# untitled.net
KiCad netlist of a schematic drawn in EAGLE
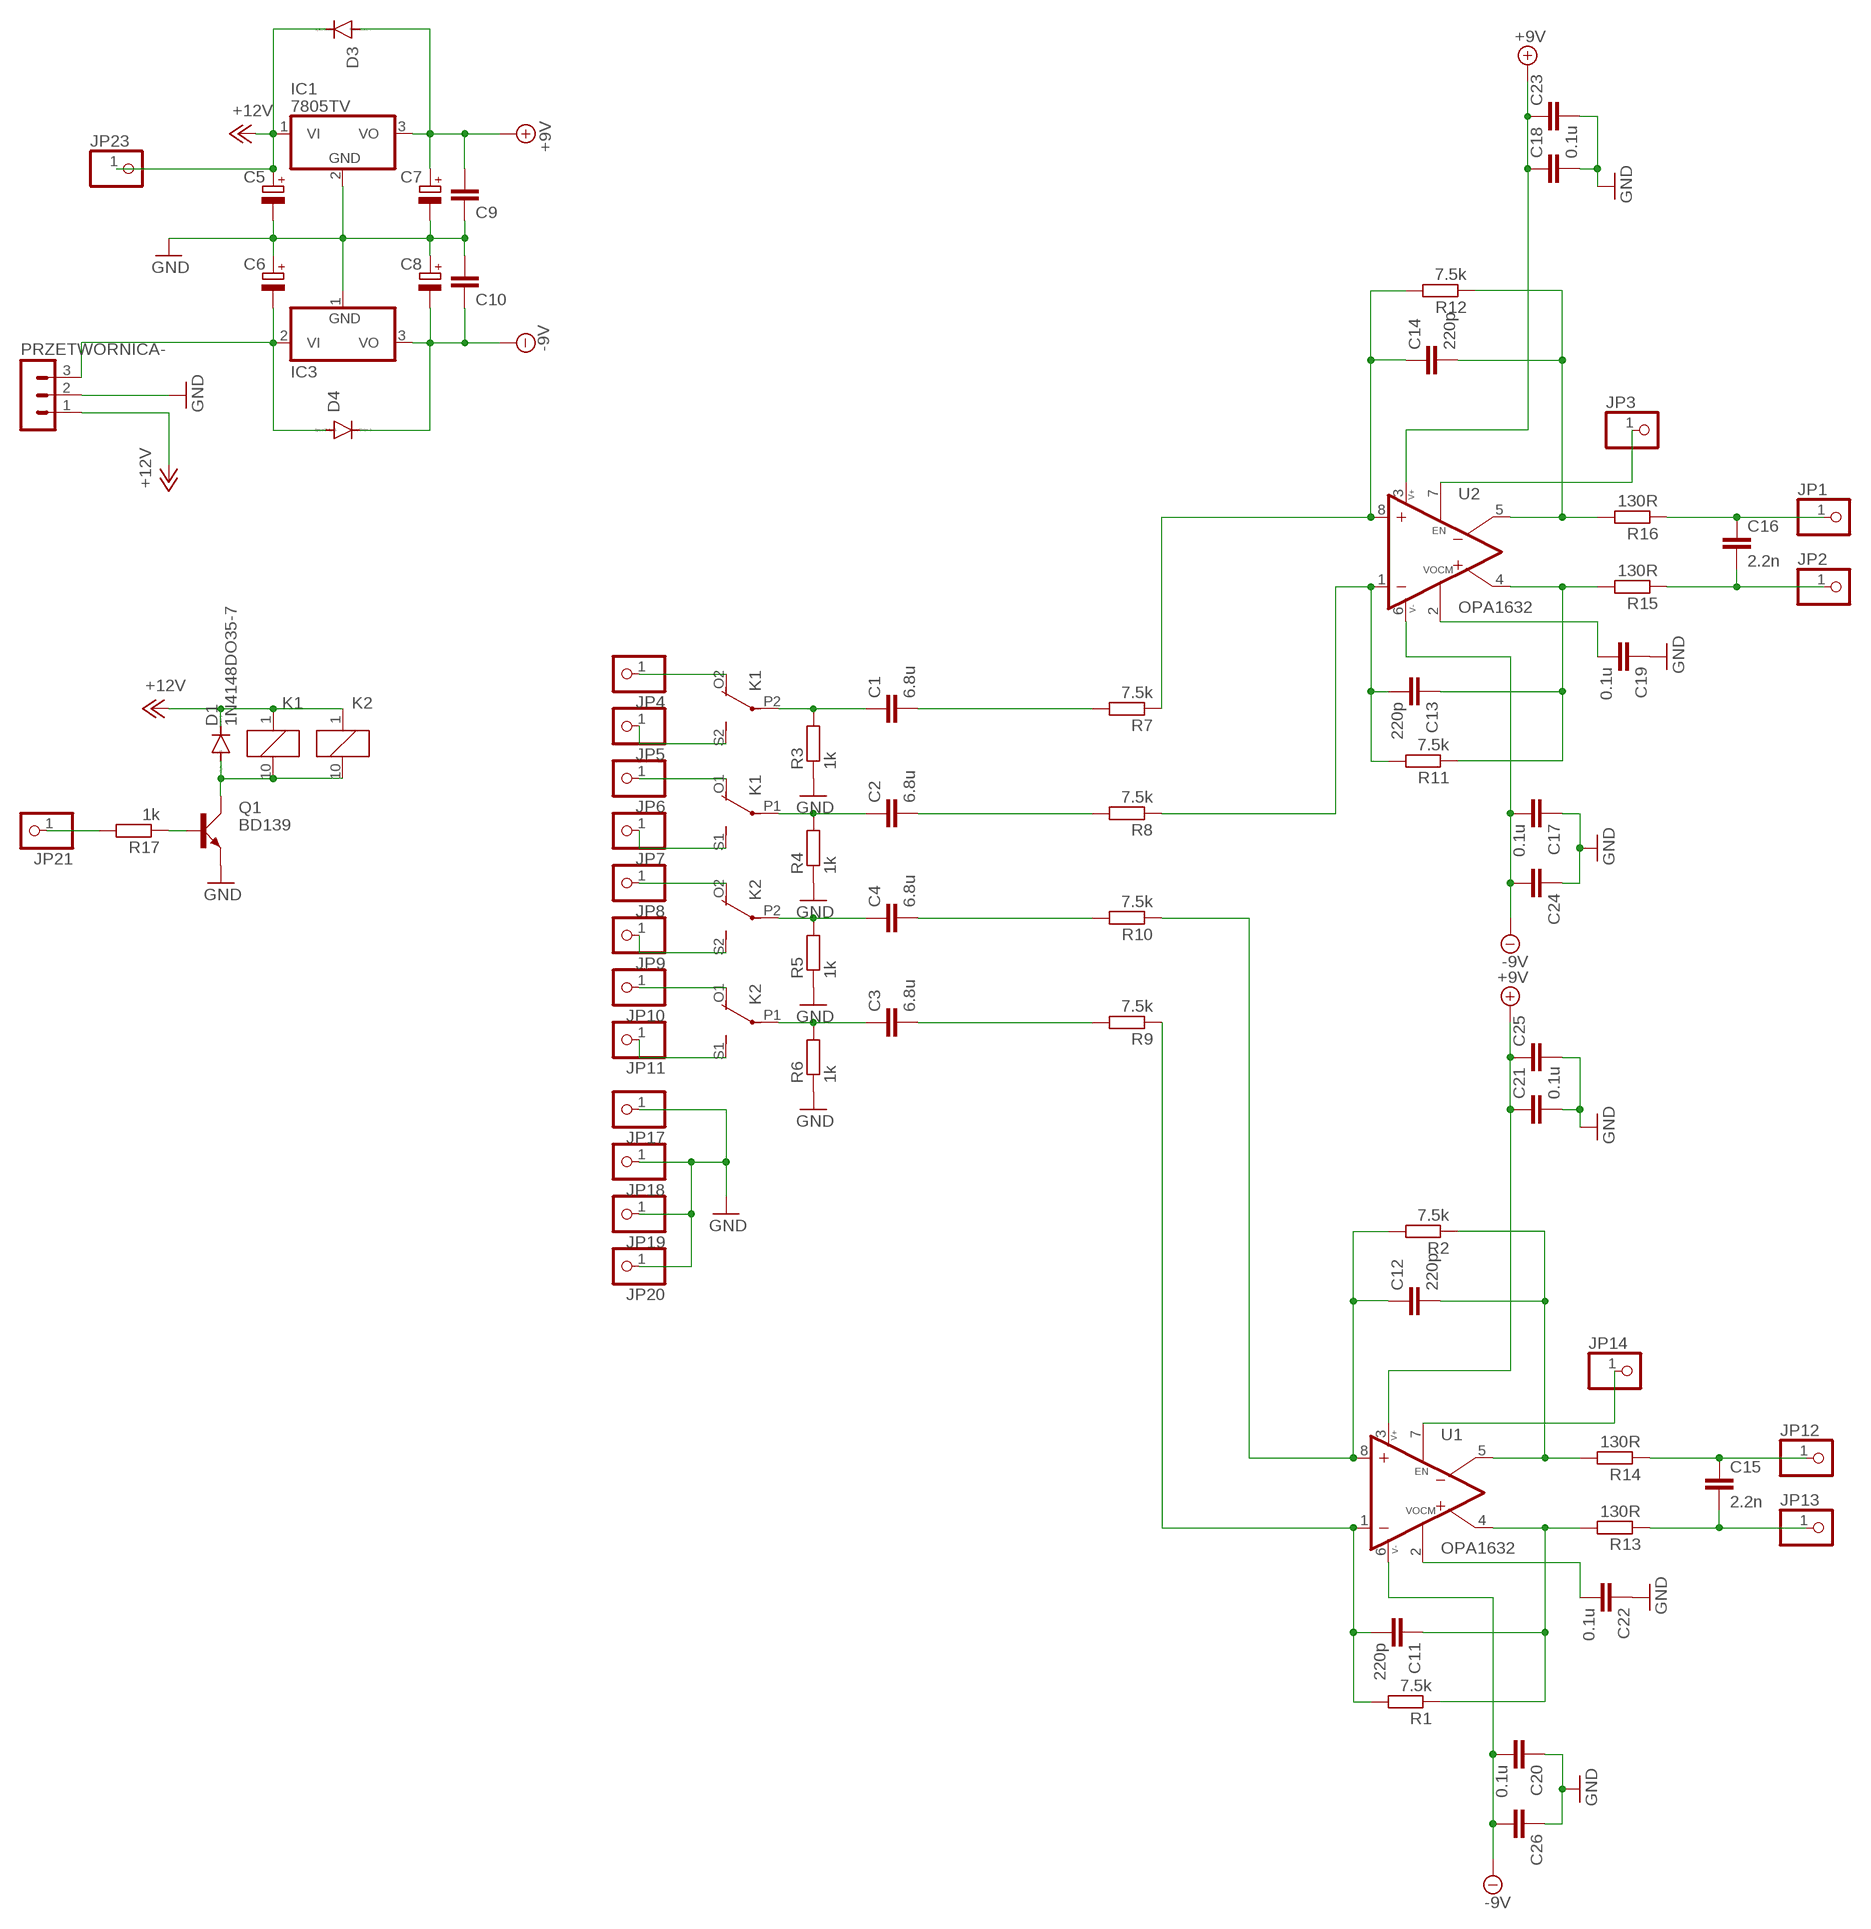
[diagram p0: schematic, sheet 1]

(export (version "E")
  (design (tool "Eeschema 10.0.6"))
  (components
    (comp (ref "C1")
      (value "6.8u")
      (footprint "eagle-import:C5B7.2")
      (libsource (lib "eagle-import") (part "C5/7.2"))
    )
    (comp (ref "C2")
      (value "6.8u")
      (footprint "eagle-import:C5B7.2")
      (libsource (lib "eagle-import") (part "C5/7.2"))
    )
    (comp (ref "C3")
      (value "6.8u")
      (footprint "eagle-import:C5B7.2")
      (libsource (lib "eagle-import") (part "C5/7.2"))
    )
    (comp (ref "C4")
      (value "6.8u")
      (footprint "eagle-import:C5B7.2")
      (libsource (lib "eagle-import") (part "C5/7.2"))
    )
    (comp (ref "C5")
      (value "CPOL-EUE3.5-8")
      (footprint "eagle-import:E3,5-8")
      (libsource (lib "eagle-import") (part "CPOL-EUE3.5-8"))
    )
    (comp (ref "C6")
      (value "CPOL-EUE3.5-8")
      (footprint "eagle-import:E3,5-8")
      (libsource (lib "eagle-import") (part "CPOL-EUE3.5-8"))
    )
    (comp (ref "C7")
      (value "CPOL-EUE3.5-8")
      (footprint "eagle-import:E3,5-8")
      (libsource (lib "eagle-import") (part "CPOL-EUE3.5-8"))
    )
    (comp (ref "C8")
      (value "CPOL-EUE3.5-8")
      (footprint "eagle-import:E3,5-8")
      (libsource (lib "eagle-import") (part "CPOL-EUE3.5-8"))
    )
    (comp (ref "C9")
      (value "C-EU050-024X044")
      (footprint "eagle-import:C050-024X044")
      (libsource (lib "eagle-import") (part "C-EU050-024X044"))
    )
    (comp (ref "C10")
      (value "C-EU050-024X044")
      (footprint "eagle-import:C050-024X044")
      (libsource (lib "eagle-import") (part "C-EU050-024X044"))
    )
    (comp (ref "C11")
      (value "220p")
      (footprint "eagle-import:C075-032X103")
      (libsource (lib "eagle-import") (part "C-EU075-032X103"))
    )
    (comp (ref "C12")
      (value "220p")
      (footprint "eagle-import:C075-032X103")
      (libsource (lib "eagle-import") (part "C-EU075-032X103"))
    )
    (comp (ref "C13")
      (value "220p")
      (footprint "eagle-import:C075-032X103")
      (libsource (lib "eagle-import") (part "C-EU075-032X103"))
    )
    (comp (ref "C14")
      (value "220p")
      (footprint "eagle-import:C075-032X103")
      (libsource (lib "eagle-import") (part "C-EU075-032X103"))
    )
    (comp (ref "C15")
      (value "2.2n")
      (footprint "eagle-import:C025-024X044")
      (libsource (lib "eagle-import") (part "C-EU025-024X044"))
    )
    (comp (ref "C16")
      (value "2.2n")
      (footprint "eagle-import:C025-024X044")
      (libsource (lib "eagle-import") (part "C-EU025-024X044"))
    )
    (comp (ref "C17")
      (value "0.1u")
      (footprint "eagle-import:C025-024X044")
      (libsource (lib "eagle-import") (part "C-EU025-024X044"))
    )
    (comp (ref "C18")
      (value "0.1u")
      (footprint "eagle-import:C025-024X044")
      (libsource (lib "eagle-import") (part "C-EU025-024X044"))
    )
    (comp (ref "C19")
      (value "0.1u")
      (footprint "eagle-import:C025-024X044")
      (libsource (lib "eagle-import") (part "C-EU025-024X044"))
    )
    (comp (ref "C20")
      (value "0.1u")
      (footprint "eagle-import:C025-024X044")
      (libsource (lib "eagle-import") (part "C-EU025-024X044"))
    )
    (comp (ref "C21")
      (value "0.1u")
      (footprint "eagle-import:C025-024X044")
      (libsource (lib "eagle-import") (part "C-EU025-024X044"))
    )
    (comp (ref "C22")
      (value "0.1u")
      (footprint "eagle-import:C025-024X044")
      (libsource (lib "eagle-import") (part "C-EU025-024X044"))
    )
    (comp (ref "C23")
      (value "C-EU050-024X044")
      (footprint "eagle-import:C050-024X044")
      (libsource (lib "eagle-import") (part "C-EU050-024X044"))
    )
    (comp (ref "C24")
      (value "C-EU050-024X044")
      (footprint "eagle-import:C050-024X044")
      (libsource (lib "eagle-import") (part "C-EU050-024X044"))
    )
    (comp (ref "C25")
      (value "C-EU050-024X044")
      (footprint "eagle-import:C050-024X044")
      (libsource (lib "eagle-import") (part "C-EU050-024X044"))
    )
    (comp (ref "C26")
      (value "C-EU050-024X044")
      (footprint "eagle-import:C050-024X044")
      (libsource (lib "eagle-import") (part "C-EU050-024X044"))
    )
    (comp (ref "D1")
      (value "1N4148DO35-7")
      (footprint "eagle-import:DO35-7")
      (libsource (lib "eagle-import") (part "1N4148DO35-7"))
    )
    (comp (ref "D3")
      (value "1N4148DO35-7")
      (footprint "eagle-import:DO35-7")
      (libsource (lib "eagle-import") (part "1N4148DO35-7"))
    )
    (comp (ref "D4")
      (value "1N4148DO35-7")
      (footprint "eagle-import:DO35-7")
      (libsource (lib "eagle-import") (part "1N4148DO35-7"))
    )
    (comp (ref "IC1")
      (value "7805TV")
      (footprint "eagle-import:TO220V")
      (libsource (lib "eagle-import") (part "78TV05"))
    )
    (comp (ref "IC3")
      (value "79")
      (footprint "eagle-import:TO220V")
      (libsource (lib "eagle-import") (part "79"))
    )
    (comp (ref "JP1")
      (value "PINHD-1X1")
      (footprint "eagle-import:1X01")
      (libsource (lib "eagle-import") (part "PINHD-1X1"))
    )
    (comp (ref "JP2")
      (value "PINHD-1X1")
      (footprint "eagle-import:1X01")
      (libsource (lib "eagle-import") (part "PINHD-1X1"))
    )
    (comp (ref "JP3")
      (value "PINHD-1X1")
      (footprint "eagle-import:1X01")
      (libsource (lib "eagle-import") (part "PINHD-1X1"))
    )
    (comp (ref "JP4")
      (value "PINHD-1X1")
      (footprint "eagle-import:1X01")
      (libsource (lib "eagle-import") (part "PINHD-1X1"))
    )
    (comp (ref "JP5")
      (value "PINHD-1X1")
      (footprint "eagle-import:1X01")
      (libsource (lib "eagle-import") (part "PINHD-1X1"))
    )
    (comp (ref "JP6")
      (value "PINHD-1X1")
      (footprint "eagle-import:1X01")
      (libsource (lib "eagle-import") (part "PINHD-1X1"))
    )
    (comp (ref "JP7")
      (value "PINHD-1X1")
      (footprint "eagle-import:1X01")
      (libsource (lib "eagle-import") (part "PINHD-1X1"))
    )
    (comp (ref "JP8")
      (value "PINHD-1X1")
      (footprint "eagle-import:1X01")
      (libsource (lib "eagle-import") (part "PINHD-1X1"))
    )
    (comp (ref "JP9")
      (value "PINHD-1X1")
      (footprint "eagle-import:1X01")
      (libsource (lib "eagle-import") (part "PINHD-1X1"))
    )
    (comp (ref "JP10")
      (value "PINHD-1X1")
      (footprint "eagle-import:1X01")
      (libsource (lib "eagle-import") (part "PINHD-1X1"))
    )
    (comp (ref "JP11")
      (value "PINHD-1X1")
      (footprint "eagle-import:1X01")
      (libsource (lib "eagle-import") (part "PINHD-1X1"))
    )
    (comp (ref "JP12")
      (value "PINHD-1X1")
      (footprint "eagle-import:1X01")
      (libsource (lib "eagle-import") (part "PINHD-1X1"))
    )
    (comp (ref "JP13")
      (value "PINHD-1X1")
      (footprint "eagle-import:1X01")
      (libsource (lib "eagle-import") (part "PINHD-1X1"))
    )
    (comp (ref "JP14")
      (value "PINHD-1X1")
      (footprint "eagle-import:1X01")
      (libsource (lib "eagle-import") (part "PINHD-1X1"))
    )
    (comp (ref "JP17")
      (value "PINHD-1X1")
      (footprint "eagle-import:1X01")
      (libsource (lib "eagle-import") (part "PINHD-1X1"))
    )
    (comp (ref "JP18")
      (value "PINHD-1X1")
      (footprint "eagle-import:1X01")
      (libsource (lib "eagle-import") (part "PINHD-1X1"))
    )
    (comp (ref "JP19")
      (value "PINHD-1X1")
      (footprint "eagle-import:1X01")
      (libsource (lib "eagle-import") (part "PINHD-1X1"))
    )
    (comp (ref "JP20")
      (value "PINHD-1X1")
      (footprint "eagle-import:1X01")
      (libsource (lib "eagle-import") (part "PINHD-1X1"))
    )
    (comp (ref "JP21")
      (value "PINHD-1X1")
      (footprint "eagle-import:1X01")
      (libsource (lib "eagle-import") (part "PINHD-1X1"))
    )
    (comp (ref "JP23")
      (value "PINHD-1X1")
      (footprint "eagle-import:1X01")
      (libsource (lib "eagle-import") (part "PINHD-1X1"))
    )
    (comp (ref "K1")
      (value "G6H2-100")
      (footprint "eagle-import:G6H2-100")
      (libsource (lib "eagle-import") (part "G6H2-100"))
    )
    (comp (ref "K2")
      (value "G6H2-100")
      (footprint "eagle-import:G6H2-100")
      (libsource (lib "eagle-import") (part "G6H2-100"))
    )
    (comp (ref "PRZETWORNICA-")
      (value "MA03-1")
      (footprint "eagle-import:MA03-1")
      (libsource (lib "eagle-import") (part "MA03-1"))
    )
    (comp (ref "Q1")
      (value "BD139")
      (footprint "eagle-import:TO126AV")
      (libsource (lib "eagle-import") (part "BD139"))
    )
    (comp (ref "R1")
      (value "7.5k")
      (footprint "eagle-import:0204_7")
      (libsource (lib "eagle-import") (part "R-EU_0204/7"))
    )
    (comp (ref "R2")
      (value "7.5k")
      (footprint "eagle-import:0204_7")
      (libsource (lib "eagle-import") (part "R-EU_0204/7"))
    )
    (comp (ref "R3")
      (value "1k")
      (footprint "eagle-import:0204_7")
      (libsource (lib "eagle-import") (part "R-EU_0204/7"))
    )
    (comp (ref "R4")
      (value "1k")
      (footprint "eagle-import:0204_7")
      (libsource (lib "eagle-import") (part "R-EU_0204/7"))
    )
    (comp (ref "R5")
      (value "1k")
      (footprint "eagle-import:0204_7")
      (libsource (lib "eagle-import") (part "R-EU_0204/7"))
    )
    (comp (ref "R6")
      (value "1k")
      (footprint "eagle-import:0204_7")
      (libsource (lib "eagle-import") (part "R-EU_0204/7"))
    )
    (comp (ref "R7")
      (value "7.5k")
      (footprint "eagle-import:0204_5")
      (libsource (lib "eagle-import") (part "R-EU_0204/5"))
    )
    (comp (ref "R8")
      (value "7.5k")
      (footprint "eagle-import:0204_5")
      (libsource (lib "eagle-import") (part "R-EU_0204/5"))
    )
    (comp (ref "R9")
      (value "7.5k")
      (footprint "eagle-import:0204_5")
      (libsource (lib "eagle-import") (part "R-EU_0204/5"))
    )
    (comp (ref "R10")
      (value "7.5k")
      (footprint "eagle-import:0204_5")
      (libsource (lib "eagle-import") (part "R-EU_0204/5"))
    )
    (comp (ref "R11")
      (value "7.5k")
      (footprint "eagle-import:0204_7")
      (libsource (lib "eagle-import") (part "R-EU_0204/7"))
    )
    (comp (ref "R12")
      (value "7.5k")
      (footprint "eagle-import:0204_7")
      (libsource (lib "eagle-import") (part "R-EU_0204/7"))
    )
    (comp (ref "R13")
      (value "130R")
      (footprint "eagle-import:0204_5")
      (libsource (lib "eagle-import") (part "R-EU_0204/5"))
    )
    (comp (ref "R14")
      (value "130R")
      (footprint "eagle-import:0204_5")
      (libsource (lib "eagle-import") (part "R-EU_0204/5"))
    )
    (comp (ref "R15")
      (value "130R")
      (footprint "eagle-import:0204_5")
      (libsource (lib "eagle-import") (part "R-EU_0204/5"))
    )
    (comp (ref "R16")
      (value "130R")
      (footprint "eagle-import:0204_5")
      (libsource (lib "eagle-import") (part "R-EU_0204/5"))
    )
    (comp (ref "R17")
      (value "1k")
      (footprint "eagle-import:0204_7")
      (libsource (lib "eagle-import") (part "R-EU_0204/7"))
    )
    (comp (ref "U1")
      (value "OPA1632")
      (footprint "eagle-import:PRZEJSCIOWKA")
      (libsource (lib "eagle-import") (part "OPA1632"))
    )
    (comp (ref "U2")
      (value "OPA1632")
      (footprint "eagle-import:PRZEJSCIOWKA")
      (libsource (lib "eagle-import") (part "OPA1632"))
    )
  )
  (nets
    (net (code "1") (name "+9V") (class "Default")
      (node (ref "C18") (pin "1") (pinfunction "1_1") (pintype "passive"))
      (node (ref "C21") (pin "1") (pinfunction "1_1") (pintype "passive"))
      (node (ref "C23") (pin "1") (pinfunction "1_1") (pintype "passive"))
      (node (ref "C25") (pin "1") (pinfunction "1_1") (pintype "passive"))
      (node (ref "C7") (pin "+") (pinfunction "+_+") (pintype "passive"))
      (node (ref "C9") (pin "2") (pinfunction "2_2") (pintype "passive"))
      (node (ref "D3") (pin "A") (pinfunction "A_A") (pintype "passive"))
      (node (ref "IC1") (pin "3") (pinfunction "VO_3") (pintype "passive"))
      (node (ref "U1") (pin "3") (pinfunction "V+_3") (pintype "power_in"))
      (node (ref "U2") (pin "3") (pinfunction "V+_3") (pintype "power_in"))
    )
    (net (code "2") (name "+12V") (class "Default")
      (node (ref "C5") (pin "+") (pinfunction "+_+") (pintype "passive"))
      (node (ref "D1") (pin "C") (pinfunction "C_C") (pintype "passive"))
      (node (ref "D3") (pin "C") (pinfunction "C_C") (pintype "passive"))
      (node (ref "IC1") (pin "1") (pinfunction "VI_1") (pintype "input"))
      (node (ref "JP23") (pin "1") (pinfunction "1_1") (pintype "passive"))
      (node (ref "K1") (pin "1") (pinfunction "1_1") (pintype "passive"))
      (node (ref "K2") (pin "1") (pinfunction "1_1") (pintype "passive"))
      (node (ref "PRZETWORNICA-") (pin "1") (pinfunction "1_1") (pintype "passive"))
    )
    (net (code "3") (name "-9V") (class "Default")
      (node (ref "C10") (pin "1") (pinfunction "1_1") (pintype "passive"))
      (node (ref "C17") (pin "2") (pinfunction "2_2") (pintype "passive"))
      (node (ref "C20") (pin "2") (pinfunction "2_2") (pintype "passive"))
      (node (ref "C24") (pin "2") (pinfunction "2_2") (pintype "passive"))
      (node (ref "C26") (pin "2") (pinfunction "2_2") (pintype "passive"))
      (node (ref "C8") (pin "-") (pinfunction "-_-") (pintype "passive"))
      (node (ref "D4") (pin "C") (pinfunction "C_C") (pintype "passive"))
      (node (ref "IC3") (pin "3") (pinfunction "VO_3") (pintype "passive"))
      (node (ref "U1") (pin "6") (pinfunction "V-_6") (pintype "power_in"))
      (node (ref "U2") (pin "6") (pinfunction "V-_6") (pintype "power_in"))
    )
    (net (code "4") (name "GND") (class "Default")
      (node (ref "C10") (pin "2") (pinfunction "2_2") (pintype "passive"))
      (node (ref "C17") (pin "1") (pinfunction "1_1") (pintype "passive"))
      (node (ref "C18") (pin "2") (pinfunction "2_2") (pintype "passive"))
      (node (ref "C19") (pin "1") (pinfunction "1_1") (pintype "passive"))
      (node (ref "C20") (pin "1") (pinfunction "1_1") (pintype "passive"))
      (node (ref "C21") (pin "2") (pinfunction "2_2") (pintype "passive"))
      (node (ref "C22") (pin "1") (pinfunction "1_1") (pintype "passive"))
      (node (ref "C23") (pin "2") (pinfunction "2_2") (pintype "passive"))
      (node (ref "C24") (pin "1") (pinfunction "1_1") (pintype "passive"))
      (node (ref "C25") (pin "2") (pinfunction "2_2") (pintype "passive"))
      (node (ref "C26") (pin "1") (pinfunction "1_1") (pintype "passive"))
      (node (ref "C5") (pin "-") (pinfunction "-_-") (pintype "passive"))
      (node (ref "C6") (pin "+") (pinfunction "+_+") (pintype "passive"))
      (node (ref "C7") (pin "-") (pinfunction "-_-") (pintype "passive"))
      (node (ref "C8") (pin "+") (pinfunction "+_+") (pintype "passive"))
      (node (ref "C9") (pin "1") (pinfunction "1_1") (pintype "passive"))
      (node (ref "IC1") (pin "2") (pinfunction "GND_2") (pintype "passive"))
      (node (ref "IC3") (pin "1") (pinfunction "GND_1") (pintype "passive"))
      (node (ref "JP17") (pin "1") (pinfunction "1_1") (pintype "passive"))
      (node (ref "JP18") (pin "1") (pinfunction "1_1") (pintype "passive"))
      (node (ref "JP19") (pin "1") (pinfunction "1_1") (pintype "passive"))
      (node (ref "JP20") (pin "1") (pinfunction "1_1") (pintype "passive"))
      (node (ref "PRZETWORNICA-") (pin "2") (pinfunction "2_2") (pintype "passive"))
      (node (ref "Q1") (pin "E") (pinfunction "E_E") (pintype "passive"))
      (node (ref "R3") (pin "1") (pinfunction "1_1") (pintype "passive"))
      (node (ref "R4") (pin "1") (pinfunction "1_1") (pintype "passive"))
      (node (ref "R5") (pin "1") (pinfunction "1_1") (pintype "passive"))
      (node (ref "R6") (pin "1") (pinfunction "1_1") (pintype "passive"))
    )
    (net (code "5") (name "Net-(C1-Pad2)") (class "Default")
      (node (ref "C1") (pin "2") (pinfunction "2_2") (pintype "passive"))
      (node (ref "R7") (pin "2") (pinfunction "2_2") (pintype "passive"))
    )
    (net (code "6") (name "Net-(C2-Pad2)") (class "Default")
      (node (ref "C2") (pin "2") (pinfunction "2_2") (pintype "passive"))
      (node (ref "R8") (pin "2") (pinfunction "2_2") (pintype "passive"))
    )
    (net (code "7") (name "Net-(C3-Pad2)") (class "Default")
      (node (ref "C3") (pin "2") (pinfunction "2_2") (pintype "passive"))
      (node (ref "R9") (pin "2") (pinfunction "2_2") (pintype "passive"))
    )
    (net (code "8") (name "Net-(C4-Pad2)") (class "Default")
      (node (ref "C4") (pin "2") (pinfunction "2_2") (pintype "passive"))
      (node (ref "R10") (pin "2") (pinfunction "2_2") (pintype "passive"))
    )
    (net (code "9") (name "Net-(C15-Pad1)") (class "Default")
      (node (ref "C15") (pin "1") (pinfunction "1_1") (pintype "passive"))
      (node (ref "JP12") (pin "1") (pinfunction "1_1") (pintype "passive"))
      (node (ref "R14") (pin "1") (pinfunction "1_1") (pintype "passive"))
    )
    (net (code "10") (name "Net-(C15-Pad2)") (class "Default")
      (node (ref "C15") (pin "2") (pinfunction "2_2") (pintype "passive"))
      (node (ref "JP13") (pin "1") (pinfunction "1_1") (pintype "passive"))
      (node (ref "R13") (pin "1") (pinfunction "1_1") (pintype "passive"))
    )
    (net (code "11") (name "Net-(C16-Pad1)") (class "Default")
      (node (ref "C16") (pin "1") (pinfunction "1_1") (pintype "passive"))
      (node (ref "JP1") (pin "1") (pinfunction "1_1") (pintype "passive"))
      (node (ref "R16") (pin "1") (pinfunction "1_1") (pintype "passive"))
    )
    (net (code "12") (name "Net-(C16-Pad2)") (class "Default")
      (node (ref "C16") (pin "2") (pinfunction "2_2") (pintype "passive"))
      (node (ref "JP2") (pin "1") (pinfunction "1_1") (pintype "passive"))
      (node (ref "R15") (pin "1") (pinfunction "1_1") (pintype "passive"))
    )
    (net (code "13") (name "Net-(IC3-VI)") (class "Default")
      (node (ref "C6") (pin "-") (pinfunction "-_-") (pintype "passive"))
      (node (ref "D4") (pin "A") (pinfunction "A_A") (pintype "passive"))
      (node (ref "IC3") (pin "2") (pinfunction "VI_2") (pintype "input"))
      (node (ref "PRZETWORNICA-") (pin "3") (pinfunction "3_3") (pintype "passive"))
    )
    (net (code "14") (name "Net-(JP21-Pad1)") (class "Default")
      (node (ref "JP21") (pin "1") (pinfunction "1_1") (pintype "passive"))
      (node (ref "R17") (pin "2") (pinfunction "2_2") (pintype "passive"))
    )
    (net (code "15") (name "Net-(K1A-2)") (class "Default")
      (node (ref "D1") (pin "A") (pinfunction "A_A") (pintype "passive"))
      (node (ref "K1") (pin "10") (pinfunction "2_10") (pintype "passive"))
      (node (ref "K2") (pin "10") (pinfunction "2_10") (pintype "passive"))
      (node (ref "Q1") (pin "C") (pinfunction "C_C") (pintype "passive"))
    )
    (net (code "16") (name "Net-(K1B-O)") (class "Default")
      (node (ref "JP6") (pin "1") (pinfunction "1_1") (pintype "passive"))
      (node (ref "K1") (pin "O1") (pinfunction "O_O1") (pintype "passive"))
    )
    (net (code "17") (name "Net-(K1B-P)") (class "Default")
      (node (ref "C2") (pin "1") (pinfunction "1_1") (pintype "passive"))
      (node (ref "K1") (pin "P1") (pinfunction "P_P1") (pintype "passive"))
      (node (ref "R4") (pin "2") (pinfunction "2_2") (pintype "passive"))
    )
    (net (code "18") (name "Net-(K1B-S)") (class "Default")
      (node (ref "JP7") (pin "1") (pinfunction "1_1") (pintype "passive"))
      (node (ref "K1") (pin "S1") (pinfunction "S_S1") (pintype "passive"))
    )
    (net (code "19") (name "Net-(K1C-O)") (class "Default")
      (node (ref "JP4") (pin "1") (pinfunction "1_1") (pintype "passive"))
      (node (ref "K1") (pin "O2") (pinfunction "O_O2") (pintype "passive"))
    )
    (net (code "20") (name "Net-(K1C-P)") (class "Default")
      (node (ref "C1") (pin "1") (pinfunction "1_1") (pintype "passive"))
      (node (ref "K1") (pin "P2") (pinfunction "P_P2") (pintype "passive"))
      (node (ref "R3") (pin "2") (pinfunction "2_2") (pintype "passive"))
    )
    (net (code "21") (name "Net-(K1C-S)") (class "Default")
      (node (ref "JP5") (pin "1") (pinfunction "1_1") (pintype "passive"))
      (node (ref "K1") (pin "S2") (pinfunction "S_S2") (pintype "passive"))
    )
    (net (code "22") (name "Net-(K2B-O)") (class "Default")
      (node (ref "JP10") (pin "1") (pinfunction "1_1") (pintype "passive"))
      (node (ref "K2") (pin "O1") (pinfunction "O_O1") (pintype "passive"))
    )
    (net (code "23") (name "Net-(K2B-P)") (class "Default")
      (node (ref "C3") (pin "1") (pinfunction "1_1") (pintype "passive"))
      (node (ref "K2") (pin "P1") (pinfunction "P_P1") (pintype "passive"))
      (node (ref "R6") (pin "2") (pinfunction "2_2") (pintype "passive"))
    )
    (net (code "24") (name "Net-(K2B-S)") (class "Default")
      (node (ref "JP11") (pin "1") (pinfunction "1_1") (pintype "passive"))
      (node (ref "K2") (pin "S1") (pinfunction "S_S1") (pintype "passive"))
    )
    (net (code "25") (name "Net-(K2C-O)") (class "Default")
      (node (ref "JP8") (pin "1") (pinfunction "1_1") (pintype "passive"))
      (node (ref "K2") (pin "O2") (pinfunction "O_O2") (pintype "passive"))
    )
    (net (code "26") (name "Net-(K2C-P)") (class "Default")
      (node (ref "C4") (pin "1") (pinfunction "1_1") (pintype "passive"))
      (node (ref "K2") (pin "P2") (pinfunction "P_P2") (pintype "passive"))
      (node (ref "R5") (pin "2") (pinfunction "2_2") (pintype "passive"))
    )
    (net (code "27") (name "Net-(K2C-S)") (class "Default")
      (node (ref "JP9") (pin "1") (pinfunction "1_1") (pintype "passive"))
      (node (ref "K2") (pin "S2") (pinfunction "S_S2") (pintype "passive"))
    )
    (net (code "28") (name "Net-(Q1-PadB)") (class "Default")
      (node (ref "Q1") (pin "B") (pinfunction "B_B") (pintype "passive"))
      (node (ref "R17") (pin "1") (pinfunction "1_1") (pintype "passive"))
    )
    (net (code "29") (name "Net-(U1-+IN)") (class "Default")
      (node (ref "C12") (pin "1") (pinfunction "1_1") (pintype "passive"))
      (node (ref "R10") (pin "1") (pinfunction "1_1") (pintype "passive"))
      (node (ref "R2") (pin "2") (pinfunction "2_2") (pintype "passive"))
      (node (ref "U1") (pin "8") (pinfunction "+IN_8") (pintype "input"))
    )
    (net (code "30") (name "Net-(U1-+OUT)") (class "Default")
      (node (ref "C11") (pin "1") (pinfunction "1_1") (pintype "passive"))
      (node (ref "R1") (pin "1") (pinfunction "1_1") (pintype "passive"))
      (node (ref "R13") (pin "2") (pinfunction "2_2") (pintype "passive"))
      (node (ref "U1") (pin "4") (pinfunction "+OUT_4") (pintype "output"))
    )
    (net (code "31") (name "Net-(U1--IN)") (class "Default")
      (node (ref "C11") (pin "2") (pinfunction "2_2") (pintype "passive"))
      (node (ref "R1") (pin "2") (pinfunction "2_2") (pintype "passive"))
      (node (ref "R9") (pin "1") (pinfunction "1_1") (pintype "passive"))
      (node (ref "U1") (pin "1") (pinfunction "-IN_1") (pintype "input"))
    )
    (net (code "32") (name "Net-(U1--OUT)") (class "Default")
      (node (ref "C12") (pin "2") (pinfunction "2_2") (pintype "passive"))
      (node (ref "R14") (pin "2") (pinfunction "2_2") (pintype "passive"))
      (node (ref "R2") (pin "1") (pinfunction "1_1") (pintype "passive"))
      (node (ref "U1") (pin "5") (pinfunction "-OUT_5") (pintype "output"))
    )
    (net (code "33") (name "Net-(U1-EN)") (class "Default")
      (node (ref "JP14") (pin "1") (pinfunction "1_1") (pintype "passive"))
      (node (ref "U1") (pin "7") (pinfunction "EN_7") (pintype "input"))
    )
    (net (code "34") (name "Net-(U1-VOCM)") (class "Default")
      (node (ref "C22") (pin "2") (pinfunction "2_2") (pintype "passive"))
      (node (ref "U1") (pin "2") (pinfunction "VOCM_2") (pintype "input"))
    )
    (net (code "35") (name "Net-(U2-+IN)") (class "Default")
      (node (ref "C14") (pin "1") (pinfunction "1_1") (pintype "passive"))
      (node (ref "R12") (pin "2") (pinfunction "2_2") (pintype "passive"))
      (node (ref "R7") (pin "1") (pinfunction "1_1") (pintype "passive"))
      (node (ref "U2") (pin "8") (pinfunction "+IN_8") (pintype "input"))
    )
    (net (code "36") (name "Net-(U2-+OUT)") (class "Default")
      (node (ref "C13") (pin "1") (pinfunction "1_1") (pintype "passive"))
      (node (ref "R11") (pin "1") (pinfunction "1_1") (pintype "passive"))
      (node (ref "R15") (pin "2") (pinfunction "2_2") (pintype "passive"))
      (node (ref "U2") (pin "4") (pinfunction "+OUT_4") (pintype "output"))
    )
    (net (code "37") (name "Net-(U2--IN)") (class "Default")
      (node (ref "C13") (pin "2") (pinfunction "2_2") (pintype "passive"))
      (node (ref "R11") (pin "2") (pinfunction "2_2") (pintype "passive"))
      (node (ref "R8") (pin "1") (pinfunction "1_1") (pintype "passive"))
      (node (ref "U2") (pin "1") (pinfunction "-IN_1") (pintype "input"))
    )
    (net (code "38") (name "Net-(U2--OUT)") (class "Default")
      (node (ref "C14") (pin "2") (pinfunction "2_2") (pintype "passive"))
      (node (ref "R12") (pin "1") (pinfunction "1_1") (pintype "passive"))
      (node (ref "R16") (pin "2") (pinfunction "2_2") (pintype "passive"))
      (node (ref "U2") (pin "5") (pinfunction "-OUT_5") (pintype "output"))
    )
    (net (code "39") (name "Net-(U2-EN)") (class "Default")
      (node (ref "JP3") (pin "1") (pinfunction "1_1") (pintype "passive"))
      (node (ref "U2") (pin "7") (pinfunction "EN_7") (pintype "input"))
    )
    (net (code "40") (name "Net-(U2-VOCM)") (class "Default")
      (node (ref "C19") (pin "2") (pinfunction "2_2") (pintype "passive"))
      (node (ref "U2") (pin "2") (pinfunction "VOCM_2") (pintype "input"))
    )
  )
)
